# Stepper_control_circuit.net
KiCad netlist of a schematic drawn in EAGLE
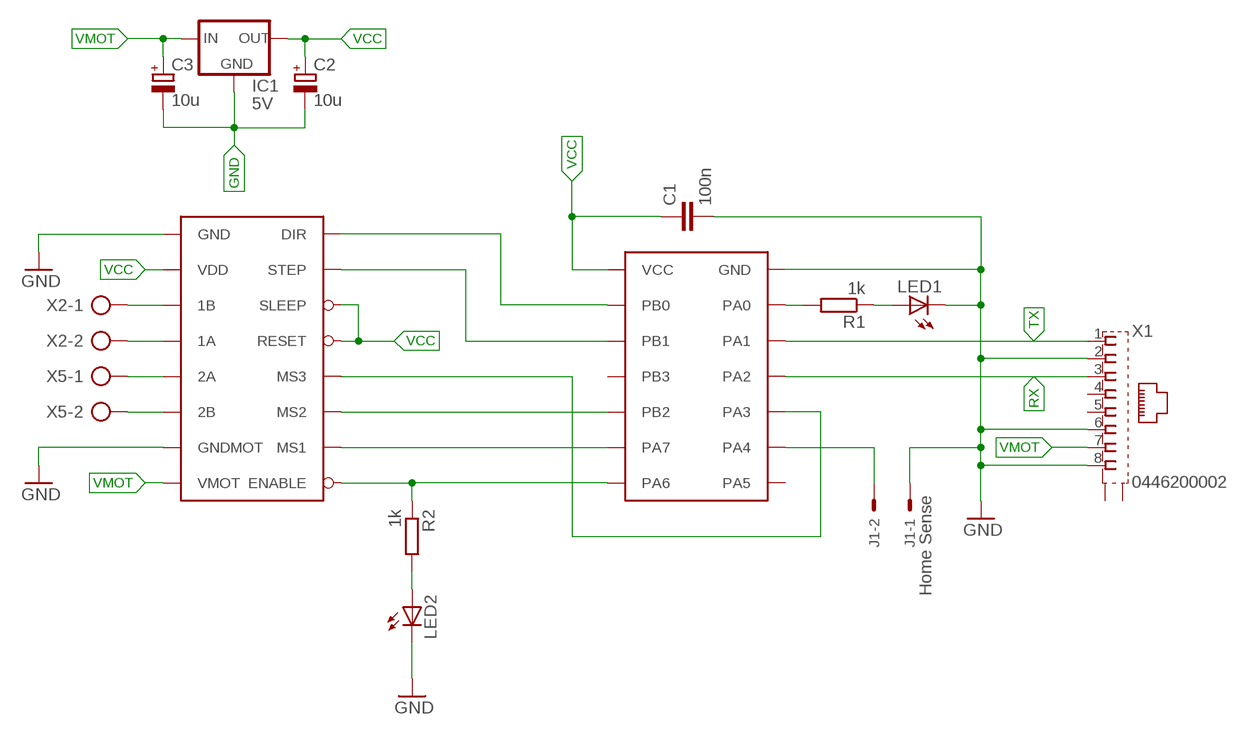
[diagram p0: schematic, sheet 1]

(export (version "E")
  (design (tool "Eeschema 10.0.6"))
  (components
    (comp (ref "C1")
      (value "100n")
      (footprint "eagle-import:C050-025X075")
      (libsource (lib "eagle-import") (part "C-EU050-025X075"))
    )
    (comp (ref "C2")
      (value "10u")
      (footprint "eagle-import:E2,5-5")
      (libsource (lib "eagle-import") (part "CPOL-EUE2.5-5"))
    )
    (comp (ref "C3")
      (value "10u")
      (footprint "eagle-import:E2,5-5")
      (libsource (lib "eagle-import") (part "CPOL-EUE2.5-5"))
    )
    (comp (ref "IC1")
      (value "5V")
      (footprint "eagle-import:TO92-CBE")
      (libsource (lib "eagle-import") (part "VOL-REG-TO92"))
    )
    (comp (ref "J1")
      (value "Home Sense")
      (footprint "eagle-import:6410-02")
      (libsource (lib "eagle-import") (part "22-?-0227-2021"))
    )
    (comp (ref "LED1")
      (value "LED3MM")
      (footprint "eagle-import:LED3MM")
      (libsource (lib "eagle-import") (part "LED3MM"))
    )
    (comp (ref "LED2")
      (value "LED3MM")
      (footprint "eagle-import:LED3MM")
      (libsource (lib "eagle-import") (part "LED3MM"))
    )
    (comp (ref "R1")
      (value "1k")
      (footprint "eagle-import:0204V")
      (libsource (lib "eagle-import") (part "R-EU_0204/2V"))
    )
    (comp (ref "R2")
      (value "1k")
      (footprint "eagle-import:0204V")
      (libsource (lib "eagle-import") (part "R-EU_0204/2V"))
    )
    (comp (ref "U$1")
      (value "ATTINY841-BOARD")
      (footprint "eagle-import:ADAPT-ATTINY841")
      (libsource (lib "eagle-import") (part "ATTINY841-BOARD"))
    )
    (comp (ref "U$2")
      (value "A4988-BOARD")
      (footprint "eagle-import:ADAPT-A4988")
      (libsource (lib "eagle-import") (part "A4988-BOARD"))
    )
    (comp (ref "X1")
      (value "0446200002")
      (footprint "eagle-import:0446200002")
      (fields (field (name "MF") "MOLEX"))
      (libsource (lib "eagle-import") (part "0446200002"))
    )
    (comp (ref "X2")
      (value "AK500/2")
      (footprint "eagle-import:AK500_2")
      (libsource (lib "eagle-import") (part "AK500/2"))
    )
    (comp (ref "X5")
      (value "AK500/2")
      (footprint "eagle-import:AK500_2")
      (libsource (lib "eagle-import") (part "AK500/2"))
    )
  )
  (nets
    (net (code "1") (name "GND") (class "Default")
      (node (ref "C1") (pin "2") (pinfunction "2_2") (pintype "passive"))
      (node (ref "C2") (pin "-") (pinfunction "-_-") (pintype "passive"))
      (node (ref "C3") (pin "-") (pinfunction "-_-") (pintype "passive"))
      (node (ref "IC1") (pin "B") (pinfunction "GND_B") (pintype "input"))
      (node (ref "J1") (pin "1") (pinfunction "S_1") (pintype "passive"))
      (node (ref "LED1") (pin "K") (pinfunction "C_K") (pintype "passive"))
      (node (ref "LED2") (pin "K") (pinfunction "C_K") (pintype "passive"))
      (node (ref "U$1") (pin "GND") (pinfunction "GND_GND") (pintype "bidirectional"))
      (node (ref "U$2") (pin "GND") (pinfunction "GND_GND") (pintype "bidirectional"))
      (node (ref "U$2") (pin "GNDMOT") (pinfunction "GNDMOT_GNDMOT") (pintype "bidirectional"))
      (node (ref "X1") (pin "2") (pinfunction "2_2") (pintype "passive"))
      (node (ref "X1") (pin "6") (pinfunction "6_6") (pintype "passive"))
      (node (ref "X1") (pin "8") (pinfunction "8_8") (pintype "passive"))
    )
    (net (code "2") (name "Net-(J1B-S)") (class "Default")
      (node (ref "J1") (pin "2") (pinfunction "S_2") (pintype "passive"))
      (node (ref "U$1") (pin "PA4") (pinfunction "PA4_PA4") (pintype "bidirectional"))
    )
    (net (code "3") (name "Net-(LED1-PadA)") (class "Default")
      (node (ref "LED1") (pin "A") (pinfunction "A_A") (pintype "passive"))
      (node (ref "R1") (pin "1") (pinfunction "1_1") (pintype "passive"))
    )
    (net (code "4") (name "Net-(LED2-PadA)") (class "Default")
      (node (ref "LED2") (pin "A") (pinfunction "A_A") (pintype "passive"))
      (node (ref "R2") (pin "2") (pinfunction "2_2") (pintype "passive"))
    )
    (net (code "5") (name "Net-(R1-Pad2)") (class "Default")
      (node (ref "R1") (pin "2") (pinfunction "2_2") (pintype "passive"))
      (node (ref "U$1") (pin "PA0") (pinfunction "PA0_PA0") (pintype "bidirectional"))
    )
    (net (code "6") (name "Net-(R2-Pad1)") (class "Default")
      (node (ref "R2") (pin "1") (pinfunction "1_1") (pintype "passive"))
      (node (ref "U$1") (pin "PA6") (pinfunction "PA6_PA6") (pintype "bidirectional"))
      (node (ref "U$2") (pin "ENABLE") (pinfunction "ENABLE_ENABLE") (pintype "bidirectional"))
    )
    (net (code "7") (name "Net-(U$1-PadPA3)") (class "Default")
      (node (ref "U$1") (pin "PA3") (pinfunction "PA3_PA3") (pintype "bidirectional"))
      (node (ref "U$2") (pin "MS3") (pinfunction "MS3_MS3") (pintype "bidirectional"))
    )
    (net (code "8") (name "Net-(U$1-PadPA7)") (class "Default")
      (node (ref "U$1") (pin "PA7") (pinfunction "PA7_PA7") (pintype "bidirectional"))
      (node (ref "U$2") (pin "MS1") (pinfunction "MS1_MS1") (pintype "bidirectional"))
    )
    (net (code "9") (name "Net-(U$1-PadPB0)") (class "Default")
      (node (ref "U$1") (pin "PB0") (pinfunction "PB0_PB0") (pintype "bidirectional"))
      (node (ref "U$2") (pin "DIR") (pinfunction "DIR_DIR") (pintype "bidirectional"))
    )
    (net (code "10") (name "Net-(U$1-PadPB1)") (class "Default")
      (node (ref "U$1") (pin "PB1") (pinfunction "PB1_PB1") (pintype "bidirectional"))
      (node (ref "U$2") (pin "STEP") (pinfunction "STEP_STEP") (pintype "bidirectional"))
    )
    (net (code "11") (name "Net-(U$1-PadPB2)") (class "Default")
      (node (ref "U$1") (pin "PB2") (pinfunction "PB2_PB2") (pintype "bidirectional"))
      (node (ref "U$2") (pin "MS2") (pinfunction "MS2_MS2") (pintype "bidirectional"))
    )
    (net (code "12") (name "Net-(X2A-KL)") (class "Default")
      (node (ref "U$2") (pin "1B") (pinfunction "1B_1B") (pintype "bidirectional"))
      (node (ref "X2") (pin "1") (pinfunction "KL_1") (pintype "passive"))
    )
    (net (code "13") (name "Net-(X2B-KL)") (class "Default")
      (node (ref "U$2") (pin "1A") (pinfunction "1A_1A") (pintype "bidirectional"))
      (node (ref "X2") (pin "2") (pinfunction "KL_2") (pintype "passive"))
    )
    (net (code "14") (name "Net-(X5A-KL)") (class "Default")
      (node (ref "U$2") (pin "2A") (pinfunction "2A_2A") (pintype "bidirectional"))
      (node (ref "X5") (pin "1") (pinfunction "KL_1") (pintype "passive"))
    )
    (net (code "15") (name "Net-(X5B-KL)") (class "Default")
      (node (ref "U$2") (pin "2B") (pinfunction "2B_2B") (pintype "bidirectional"))
      (node (ref "X5") (pin "2") (pinfunction "KL_2") (pintype "passive"))
    )
    (net (code "16") (name "RX") (class "Default")
      (node (ref "U$1") (pin "PA2") (pinfunction "PA2_PA2") (pintype "bidirectional"))
      (node (ref "X1") (pin "3") (pinfunction "3_3") (pintype "passive"))
    )
    (net (code "17") (name "TX") (class "Default")
      (node (ref "U$1") (pin "PA1") (pinfunction "PA1_PA1") (pintype "bidirectional"))
      (node (ref "X1") (pin "1") (pinfunction "1_1") (pintype "passive"))
    )
    (net (code "18") (name "VCC") (class "Default")
      (node (ref "C1") (pin "1") (pinfunction "1_1") (pintype "passive"))
      (node (ref "C2") (pin "+") (pinfunction "+_+") (pintype "passive"))
      (node (ref "IC1") (pin "C") (pinfunction "OUT_C") (pintype "passive"))
      (node (ref "U$1") (pin "VCC") (pinfunction "VCC_VCC") (pintype "bidirectional"))
      (node (ref "U$2") (pin "RESET") (pinfunction "RESET_RESET") (pintype "bidirectional"))
      (node (ref "U$2") (pin "SLEEP") (pinfunction "SLEEP_SLEEP") (pintype "bidirectional"))
      (node (ref "U$2") (pin "VDD") (pinfunction "VDD_VDD") (pintype "bidirectional"))
    )
    (net (code "19") (name "VMOT") (class "Default")
      (node (ref "C3") (pin "+") (pinfunction "+_+") (pintype "passive"))
      (node (ref "IC1") (pin "E") (pinfunction "IN_E") (pintype "input"))
      (node (ref "U$2") (pin "VMOT") (pinfunction "VMOT_VMOT") (pintype "bidirectional"))
      (node (ref "X1") (pin "7") (pinfunction "7_7") (pintype "passive"))
    )
    (net (code "20") (name "unconnected-(U$1-PadPA5)") (class "Default")
      (node (ref "U$1") (pin "PA5") (pinfunction "PA5_PA5") (pintype "bidirectional"))
    )
    (net (code "21") (name "unconnected-(U$1-PadPB3)") (class "Default")
      (node (ref "U$1") (pin "PB3") (pinfunction "PB3_PB3") (pintype "bidirectional"))
    )
    (net (code "22") (name "unconnected-(X1-Pad4)") (class "Default")
      (node (ref "X1") (pin "4") (pinfunction "4_4") (pintype "passive"))
    )
    (net (code "23") (name "unconnected-(X1-Pad5)") (class "Default")
      (node (ref "X1") (pin "5") (pinfunction "5_5") (pintype "passive"))
    )
    (net (code "24") (name "unconnected-(X1-S1-PadS@1)") (class "Default")
      (node (ref "X1") (pin "S@1") (pinfunction "S1_S@1") (pintype "passive"))
    )
    (net (code "25") (name "unconnected-(X1-S2-PadS@2)") (class "Default")
      (node (ref "X1") (pin "S@2") (pinfunction "S2_S@2") (pintype "passive"))
    )
  )
)
